# tay_cam.net
KiCad netlist of a schematic drawn in Altium Designer
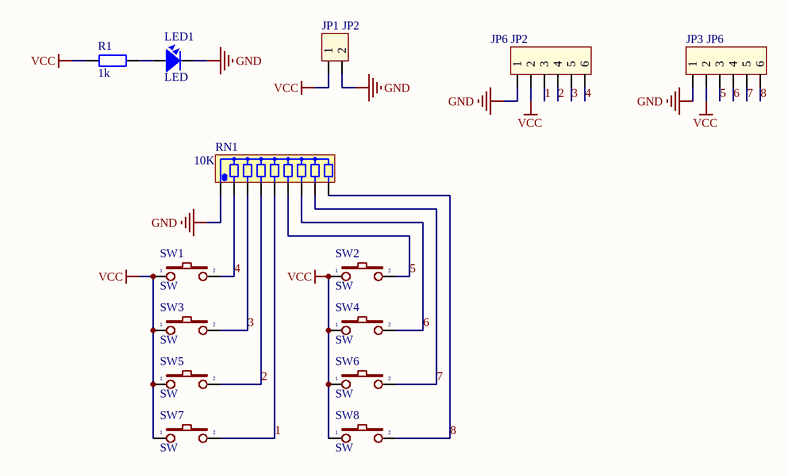
[diagram p0: tay cam.SchDoc]

(export (version "E")
  (design (tool "Eeschema 10.0.6"))
  (components
    (comp (ref "JP1")
      (value "JP2")
      (footprint "CON2")
      (description "Connector 2")
      (libsource (lib "syhaunguyen") (part "Con2"))
    )
    (comp (ref "JP2")
      (value "JP6")
      (footprint "CON6")
      (description "Connector 6")
      (libsource (lib "syhaunguyen") (part "Con6"))
    )
    (comp (ref "JP3")
      (value "JP6")
      (footprint "CON6")
      (description "Connector 6")
      (libsource (lib "syhaunguyen") (part "Con6"))
    )
    (comp (ref "LED1")
      (value "LED")
      (footprint "LED-3")
      (description "Led  Vuong")
      (libsource (lib "syhaunguyen") (part "LED"))
    )
    (comp (ref "R1")
      (value "1k")
      (footprint "R1/4W")
      (description "Resistor 1/4W")
      (libsource (lib "syhaunguyen") (part "R1/4W"))
    )
    (comp (ref "RN1")
      (value "10K")
      (footprint "RN8")
      (description "Resistor 8 (Thanh)")
      (libsource (lib "syhaunguyen") (part "RN8"))
    )
    (comp (ref "SW1")
      (value "SW")
      (footprint "SW4")
      (description "Switch button 2 pin")
      (libsource (lib "syhaunguyen") (part "SW2"))
    )
    (comp (ref "SW2")
      (value "SW")
      (footprint "SW4")
      (description "Switch button 2 pin")
      (libsource (lib "syhaunguyen") (part "SW2"))
    )
    (comp (ref "SW3")
      (value "SW")
      (footprint "SW4")
      (description "Switch button 2 pin")
      (libsource (lib "syhaunguyen") (part "SW2"))
    )
    (comp (ref "SW4")
      (value "SW")
      (footprint "SW4")
      (description "Switch button 2 pin")
      (libsource (lib "syhaunguyen") (part "SW2"))
    )
    (comp (ref "SW5")
      (value "SW")
      (footprint "SW4")
      (description "Switch button 2 pin")
      (libsource (lib "syhaunguyen") (part "SW2"))
    )
    (comp (ref "SW6")
      (value "SW")
      (footprint "SW4")
      (description "Switch button 2 pin")
      (libsource (lib "syhaunguyen") (part "SW2"))
    )
    (comp (ref "SW7")
      (value "SW")
      (footprint "SW4")
      (description "Switch button 2 pin")
      (libsource (lib "syhaunguyen") (part "SW2"))
    )
    (comp (ref "SW8")
      (value "SW")
      (footprint "SW4")
      (description "Switch button 2 pin")
      (libsource (lib "syhaunguyen") (part "SW2"))
    )
  )
  (nets
    (net (code "1") (name "/1") (class "Default")
      (node (ref "JP2") (pin "3") (pinfunction "3_3") (pintype "passive"))
      (node (ref "RN1") (pin "5") (pinfunction "5_5") (pintype "passive"))
      (node (ref "SW7") (pin "2") (pinfunction "2_2") (pintype "passive"))
    )
    (net (code "2") (name "/2") (class "Default")
      (node (ref "JP2") (pin "4") (pinfunction "4_4") (pintype "passive"))
      (node (ref "RN1") (pin "4") (pinfunction "4_4") (pintype "passive"))
      (node (ref "SW5") (pin "2") (pinfunction "2_2") (pintype "passive"))
    )
    (net (code "3") (name "/3") (class "Default")
      (node (ref "JP2") (pin "5") (pinfunction "5_5") (pintype "passive"))
      (node (ref "RN1") (pin "3") (pinfunction "3_3") (pintype "passive"))
      (node (ref "SW3") (pin "2") (pinfunction "2_2") (pintype "passive"))
    )
    (net (code "4") (name "/4") (class "Default")
      (node (ref "JP2") (pin "6") (pinfunction "6_6") (pintype "passive"))
      (node (ref "RN1") (pin "2") (pinfunction "2_2") (pintype "passive"))
      (node (ref "SW1") (pin "2") (pinfunction "2_2") (pintype "passive"))
    )
    (net (code "5") (name "/5") (class "Default")
      (node (ref "JP3") (pin "3") (pinfunction "3_3") (pintype "passive"))
      (node (ref "RN1") (pin "6") (pinfunction "6_6") (pintype "passive"))
      (node (ref "SW2") (pin "2") (pinfunction "2_2") (pintype "passive"))
    )
    (net (code "6") (name "/6") (class "Default")
      (node (ref "JP3") (pin "4") (pinfunction "4_4") (pintype "passive"))
      (node (ref "RN1") (pin "7") (pinfunction "7_7") (pintype "passive"))
      (node (ref "SW4") (pin "2") (pinfunction "2_2") (pintype "passive"))
    )
    (net (code "7") (name "/7") (class "Default")
      (node (ref "JP3") (pin "5") (pinfunction "5_5") (pintype "passive"))
      (node (ref "RN1") (pin "8") (pinfunction "8_8") (pintype "passive"))
      (node (ref "SW6") (pin "2") (pinfunction "2_2") (pintype "passive"))
    )
    (net (code "8") (name "/8") (class "Default")
      (node (ref "JP3") (pin "6") (pinfunction "6_6") (pintype "passive"))
      (node (ref "RN1") (pin "9") (pinfunction "9_9") (pintype "passive"))
      (node (ref "SW8") (pin "2") (pinfunction "2_2") (pintype "passive"))
    )
    (net (code "9") (name "GND") (class "Default")
      (node (ref "JP1") (pin "2") (pinfunction "2_2") (pintype "passive"))
      (node (ref "JP2") (pin "1") (pinfunction "1_1") (pintype "passive"))
      (node (ref "JP3") (pin "1") (pinfunction "1_1") (pintype "passive"))
      (node (ref "LED1") (pin "2") (pinfunction "2_2") (pintype "passive"))
      (node (ref "RN1") (pin "1") (pinfunction "1_1") (pintype "passive"))
    )
    (net (code "10") (name "Net-(LED1-Pad1)") (class "Default")
      (node (ref "LED1") (pin "1") (pinfunction "1_1") (pintype "passive"))
      (node (ref "R1") (pin "2") (pinfunction "2_2") (pintype "passive"))
    )
    (net (code "11") (name "VCC") (class "Default")
      (node (ref "JP1") (pin "1") (pinfunction "1_1") (pintype "passive"))
      (node (ref "JP2") (pin "2") (pinfunction "2_2") (pintype "passive"))
      (node (ref "JP3") (pin "2") (pinfunction "2_2") (pintype "passive"))
      (node (ref "R1") (pin "1") (pinfunction "1_1") (pintype "passive"))
      (node (ref "SW1") (pin "1") (pinfunction "1_1") (pintype "passive"))
      (node (ref "SW2") (pin "1") (pinfunction "1_1") (pintype "passive"))
      (node (ref "SW3") (pin "1") (pinfunction "1_1") (pintype "passive"))
      (node (ref "SW4") (pin "1") (pinfunction "1_1") (pintype "passive"))
      (node (ref "SW5") (pin "1") (pinfunction "1_1") (pintype "passive"))
      (node (ref "SW6") (pin "1") (pinfunction "1_1") (pintype "passive"))
      (node (ref "SW7") (pin "1") (pinfunction "1_1") (pintype "passive"))
      (node (ref "SW8") (pin "1") (pinfunction "1_1") (pintype "passive"))
    )
  )
)
